# power.net
KiCad netlist of a schematic drawn in Altium Designer
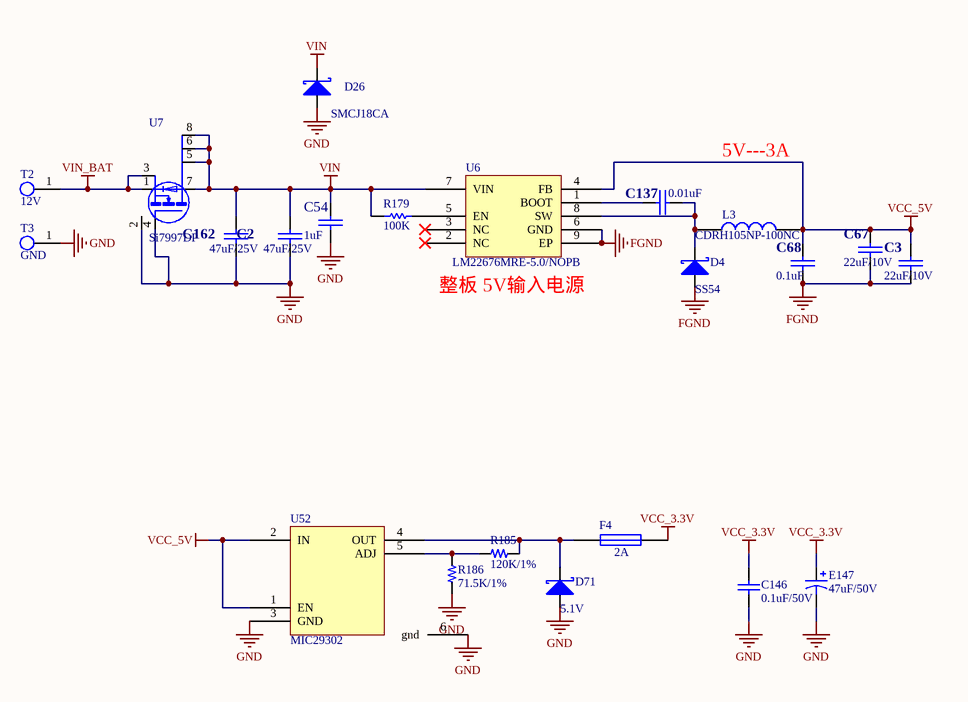
[diagram p0: power.SchDoc]

(export (version "E")
  (design (tool "Eeschema 10.0.6"))
  (components
    (comp (ref "C2")
      (value "47uF/25V")
      (footprint "1210C")
      (description "Capacitor")
      (libsource (lib "*") (part "CAP"))
    )
    (comp (ref "C3")
      (value "22uF/10V")
      (footprint "1210C")
      (description "Capacitor")
      (libsource (lib "*") (part "CAP"))
    )
    (comp (ref "C54")
      (value "1uF")
      (footprint "0603C")
      (description "Capacitor")
      (libsource (lib "*") (part "CAP"))
    )
    (comp (ref "C67")
      (value "22uF/10V")
      (footprint "1210C")
      (description "Capacitor")
      (libsource (lib "*") (part "CAP"))
    )
    (comp (ref "C68")
      (value "0.1uF")
      (footprint "0603C")
      (description "Capacitor")
      (libsource (lib "*") (part "CAP"))
    )
    (comp (ref "C137")
      (value "0.01uF")
      (footprint "0603C")
      (description "Capacitor")
      (libsource (lib "*") (part "CAP"))
    )
    (comp (ref "C146")
      (value "0.1uF/50V")
      (footprint "0603C")
      (description "Capacitor")
      (fields (field (name "PUBLISHER") "Altium Limited"))
      (libsource (lib "Miscellaneous Devices") (part "Cap"))
    )
    (comp (ref "C162")
      (value "47uF/25V")
      (footprint "1210C")
      (description "Capacitor")
      (libsource (lib "*") (part "CAP"))
    )
    (comp (ref "D4")
      (value "SS54")
      (footprint "SMC")
      (description "Schottky Diode")
      (libsource (lib "*") (part "DIODE S"))
    )
    (comp (ref "D26")
      (value "SMCJ18CA")
      (footprint "SMC")
      (description "Schottky Diode")
      (libsource (lib "*") (part "DIODE S"))
    )
    (comp (ref "D71")
      (value "5.1V")
      (footprint "SMA")
      (description "Schottky Diode")
      (libsource (lib "*") (part "DIODE S"))
    )
    (comp (ref "E147")
      (value "47uF/50V")
      (footprint "Φ10×10")
      (description "Polarized Capacitor (Radial)")
      (fields (field (name "PUBLISHER") "Altium Limited"))
      (libsource (lib "Miscellaneous Devices") (part "Cap Pol1"))
    )
    (comp (ref "F4")
      (value "2A")
      (footprint "1812-F")
      (description "Fuse")
      (fields (field (name "PUBLISHER") "Altium Limited"))
      (libsource (lib "Miscellaneous Devices") (part "Fuse 1"))
    )
    (comp (ref "L3") (value "CDRH105NP-100NC") (footprint "CDRH105") (libsource (lib "*") (part "INDUCTOR")))
    (comp (ref "R179")
      (value "100K")
      (footprint "0603R")
      (description "Resistor")
      (fields (field (name "PUBLISHER") "Altium Limited"))
      (libsource (lib "Miscellaneous Devices") (part "Res1"))
    )
    (comp (ref "R185")
      (value "120K/1%")
      (footprint "0603R")
      (description "R")
      (libsource (lib "JRJ_1") (part "R"))
    )
    (comp (ref "R186")
      (value "71.5K/1%")
      (footprint "0603R")
      (description "R")
      (libsource (lib "JRJ_1") (part "R"))
    )
    (comp (ref "T2") (value "12V") (footprint "FIX-4.5") (libsource (lib "Schlib_20110825") (part "TP")))
    (comp (ref "T3") (value "GND") (footprint "FIX-4.5") (libsource (lib "Schlib_20110825") (part "TP")))
    (comp (ref "U6")
      (value "LM22676MRE-5.0/NOPB")
      (footprint "SOP127P600X168_HS-8N")
      (libsource (lib "Schlib1") (part "LM22676MR-5.0"))
    )
    (comp (ref "U7")
      (value "Si7997DP")
      (footprint "SC-70(PowerPAK)")
      (description "Sia430DJ")
      (libsource (lib "Schlib_20110825") (part "Si7997DP"))
    )
    (comp (ref "U52")
      (value "MIC29302")
      (footprint "TO228P1435X457-6N")
      (libsource (lib "power") (part "MIC29302"))
    )
  )
  (nets
    (net (code "1") (name "FGND") (class "Default")
      (node (ref "C3") (pin "2") (pinfunction "2_2") (pintype "passive"))
      (node (ref "C67") (pin "2") (pinfunction "2_2") (pintype "passive"))
      (node (ref "C68") (pin "2") (pinfunction "2_2") (pintype "passive"))
      (node (ref "D4") (pin "1") (pinfunction "A_1") (pintype "passive"))
      (node (ref "U6") (pin "6") (pinfunction "GND_6") (pintype "passive"))
      (node (ref "U6") (pin "9") (pinfunction "EP_9") (pintype "passive"))
    )
    (net (code "2") (name "GND") (class "Default")
      (node (ref "C146") (pin "1") (pinfunction "1_1") (pintype "passive"))
      (node (ref "C162") (pin "2") (pinfunction "2_2") (pintype "passive"))
      (node (ref "C2") (pin "2") (pinfunction "2_2") (pintype "passive"))
      (node (ref "C54") (pin "1") (pinfunction "1_1") (pintype "passive"))
      (node (ref "D26") (pin "1") (pinfunction "A_1") (pintype "passive"))
      (node (ref "D71") (pin "1") (pinfunction "A_1") (pintype "passive"))
      (node (ref "E147") (pin "2") (pinfunction "2_2") (pintype "passive"))
      (node (ref "R186") (pin "1") (pintype "passive"))
      (node (ref "T3") (pin "1") (pintype "passive"))
      (node (ref "U52") (pin "3") (pinfunction "GND_3") (pintype "passive"))
      (node (ref "U52") (pin "6") (pinfunction "gnd_6") (pintype "passive"))
      (node (ref "U7") (pin "2") (pinfunction "G_2") (pintype "passive"))
      (node (ref "U7") (pin "4") (pinfunction "G_4") (pintype "passive"))
    )
    (net (code "3") (name "Net-(D4-K)") (class "Default")
      (node (ref "C137") (pin "1") (pinfunction "1_1") (pintype "passive"))
      (node (ref "D4") (pin "2") (pinfunction "K_2") (pintype "passive"))
      (node (ref "L3") (pin "1") (pinfunction "1_1") (pintype "passive"))
      (node (ref "U6") (pin "8") (pinfunction "SW_8") (pintype "passive"))
    )
    (net (code "4") (name "Net-(D71-K)") (class "Default")
      (node (ref "D71") (pin "2") (pinfunction "K_2") (pintype "passive"))
      (node (ref "F4") (pin "1") (pinfunction "1_1") (pintype "passive"))
      (node (ref "R185") (pin "1") (pintype "passive"))
      (node (ref "U52") (pin "4") (pinfunction "OUT_4") (pintype "passive"))
    )
    (net (code "5") (name "Net-(U6-BOOT)") (class "Default")
      (node (ref "C137") (pin "2") (pinfunction "2_2") (pintype "passive"))
      (node (ref "U6") (pin "1") (pinfunction "BOOT_1") (pintype "passive"))
    )
    (net (code "6") (name "Net-(U6-EN)") (class "Default")
      (node (ref "R179") (pin "1") (pinfunction "1_1") (pintype "passive"))
      (node (ref "U6") (pin "5") (pinfunction "EN_5") (pintype "passive"))
    )
    (net (code "7") (name "Net-(U52-ADJ)") (class "Default")
      (node (ref "R185") (pin "2") (pintype "passive"))
      (node (ref "R186") (pin "2") (pintype "passive"))
      (node (ref "U52") (pin "5") (pinfunction "ADJ_5") (pintype "passive"))
    )
    (net (code "8") (name "VCC_3.3V") (class "Default")
      (node (ref "C146") (pin "2") (pinfunction "2_2") (pintype "passive"))
      (node (ref "E147") (pin "1") (pinfunction "1_1") (pintype "passive"))
      (node (ref "F4") (pin "2") (pinfunction "2_2") (pintype "passive"))
    )
    (net (code "9") (name "VCC_5V") (class "Default")
      (node (ref "C3") (pin "1") (pinfunction "1_1") (pintype "passive"))
      (node (ref "C67") (pin "1") (pinfunction "1_1") (pintype "passive"))
      (node (ref "C68") (pin "1") (pinfunction "1_1") (pintype "passive"))
      (node (ref "L3") (pin "2") (pinfunction "2_2") (pintype "passive"))
      (node (ref "U52") (pin "1") (pinfunction "EN_1") (pintype "passive"))
      (node (ref "U52") (pin "2") (pinfunction "IN_2") (pintype "passive"))
      (node (ref "U6") (pin "4") (pinfunction "FB_4") (pintype "passive"))
    )
    (net (code "10") (name "VIN") (class "Default")
      (node (ref "C162") (pin "1") (pinfunction "1_1") (pintype "passive"))
      (node (ref "C2") (pin "1") (pinfunction "1_1") (pintype "passive"))
      (node (ref "C54") (pin "2") (pinfunction "2_2") (pintype "passive"))
      (node (ref "D26") (pin "2") (pinfunction "K_2") (pintype "passive"))
      (node (ref "R179") (pin "2") (pinfunction "2_2") (pintype "passive"))
      (node (ref "U6") (pin "7") (pinfunction "VIN_7") (pintype "passive"))
      (node (ref "U7") (pin "5") (pinfunction "D_5") (pintype "passive"))
      (node (ref "U7") (pin "6") (pinfunction "D_6") (pintype "passive"))
      (node (ref "U7") (pin "7") (pinfunction "D_7") (pintype "passive"))
      (node (ref "U7") (pin "8") (pinfunction "D_8") (pintype "passive"))
    )
    (net (code "11") (name "VIN_BAT") (class "Default")
      (node (ref "T2") (pin "1") (pintype "passive"))
      (node (ref "U7") (pin "1") (pinfunction "S_1") (pintype "passive"))
      (node (ref "U7") (pin "3") (pinfunction "S_3") (pintype "passive"))
    )
    (net (code "12") (name "unconnected-(U6-NC-Pad2)") (class "Default")
      (node (ref "U6") (pin "2") (pinfunction "NC_2") (pintype "passive+no_connect"))
    )
    (net (code "13") (name "unconnected-(U6-NC-Pad3)") (class "Default")
      (node (ref "U6") (pin "3") (pinfunction "NC_3") (pintype "passive+no_connect"))
    )
  )
)
